# ME433_songwei.net
KiCad netlist of a schematic drawn in EAGLE
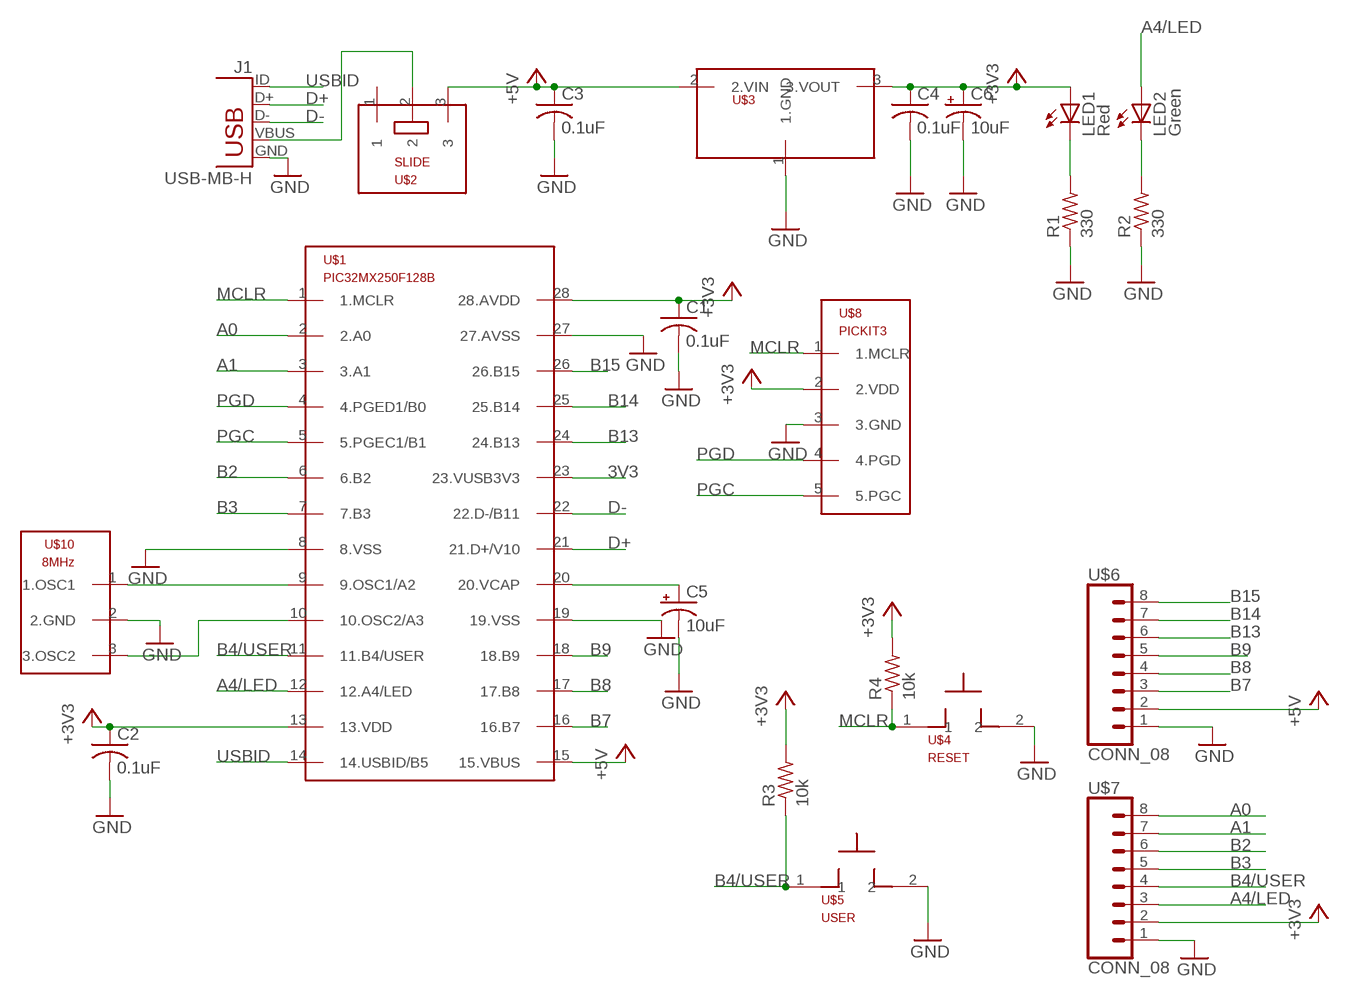
[diagram p0: schematic, sheet 1]

(export (version "E")
  (design (tool "Eeschema 10.0.6"))
  (components
    (comp (ref "C1")
      (value "0.1uF")
      (footprint "eagle-import:C025-025X050")
      (libsource (lib "eagle-import") (part "C-US025-025X050"))
    )
    (comp (ref "C2")
      (value "0.1uF")
      (footprint "eagle-import:C025-025X050")
      (libsource (lib "eagle-import") (part "C-US025-025X050"))
    )
    (comp (ref "C3")
      (value "0.1uF")
      (footprint "eagle-import:C025-025X050")
      (libsource (lib "eagle-import") (part "C-US025-025X050"))
    )
    (comp (ref "C4")
      (value "0.1uF")
      (footprint "eagle-import:C025-025X050")
      (libsource (lib "eagle-import") (part "C-US025-025X050"))
    )
    (comp (ref "C5")
      (value "10uF")
      (footprint "eagle-import:B45181B")
      (libsource (lib "eagle-import") (part "CPOL-USB45181B"))
    )
    (comp (ref "C6")
      (value "10uF")
      (footprint "eagle-import:B45181B")
      (libsource (lib "eagle-import") (part "CPOL-USB45181B"))
    )
    (comp (ref "J1")
      (value "USB-MB-H")
      (footprint "eagle-import:USB-MB-H")
      (libsource (lib "eagle-import") (part "USB-MB-H"))
    )
    (comp (ref "LED1")
      (value "Red")
      (footprint "eagle-import:LED3MM")
      (libsource (lib "eagle-import") (part "LED3MM"))
    )
    (comp (ref "LED2")
      (value "Green")
      (footprint "eagle-import:LED3MM")
      (libsource (lib "eagle-import") (part "LED3MM"))
    )
    (comp (ref "R1")
      (value "330")
      (footprint "eagle-import:0207_10")
      (libsource (lib "eagle-import") (part "R-US_0207/10"))
    )
    (comp (ref "R2")
      (value "330")
      (footprint "eagle-import:0207_10")
      (libsource (lib "eagle-import") (part "R-US_0207/10"))
    )
    (comp (ref "R3")
      (value "10k")
      (footprint "eagle-import:0207_10")
      (libsource (lib "eagle-import") (part "R-US_0207/10"))
    )
    (comp (ref "R4")
      (value "10k")
      (footprint "eagle-import:0207_10")
      (libsource (lib "eagle-import") (part "R-US_0207/10"))
    )
    (comp (ref "U$1")
      (value "PIC32MX250F128B")
      (footprint "eagle-import:DIL28-3")
      (libsource (lib "eagle-import") (part "PIC32MX250F128B"))
    )
    (comp (ref "U$2")
      (value "SLIDE")
      (footprint "eagle-import:SLIDE")
      (libsource (lib "eagle-import") (part "SLIDE"))
    )
    (comp (ref "U$3")
      (value "MCP1702")
      (footprint "eagle-import:TO92")
      (libsource (lib "eagle-import") (part "MCP1702"))
    )
    (comp (ref "U$4")
      (value "RESET")
      (footprint "eagle-import:PB")
      (libsource (lib "eagle-import") (part "PB"))
    )
    (comp (ref "U$5")
      (value "USER")
      (footprint "eagle-import:PB")
      (libsource (lib "eagle-import") (part "PB"))
    )
    (comp (ref "U$6")
      (value "CONN_08")
      (footprint "eagle-import:1X08")
      (libsource (lib "eagle-import") (part "CONN_08"))
    )
    (comp (ref "U$7")
      (value "CONN_08")
      (footprint "eagle-import:1X08")
      (libsource (lib "eagle-import") (part "CONN_08"))
    )
    (comp (ref "U$8")
      (value "PICKIT3")
      (footprint "eagle-import:1X05")
      (libsource (lib "eagle-import") (part "PICKIT3"))
    )
    (comp (ref "U$10")
      (value "8MHz")
      (footprint "eagle-import:OSC")
      (libsource (lib "eagle-import") (part "OSC"))
    )
  )
  (nets
    (net (code "1") (name "+3V3") (class "Default")
      (node (ref "C1") (pin "1") (pinfunction "1_1") (pintype "passive"))
      (node (ref "C2") (pin "1") (pinfunction "1_1") (pintype "passive"))
      (node (ref "C4") (pin "1") (pinfunction "1_1") (pintype "passive"))
      (node (ref "C6") (pin "+") (pinfunction "+_+") (pintype "passive"))
      (node (ref "LED1") (pin "A") (pinfunction "A_A") (pintype "passive"))
      (node (ref "R3") (pin "2") (pinfunction "2_2") (pintype "passive"))
      (node (ref "R4") (pin "2") (pinfunction "2_2") (pintype "passive"))
      (node (ref "U$1") (pin "13") (pinfunction "13.VDD_13") (pintype "bidirectional"))
      (node (ref "U$1") (pin "28") (pinfunction "28.AVDD_28") (pintype "bidirectional"))
      (node (ref "U$3") (pin "3") (pinfunction "3.VOUT_3") (pintype "bidirectional"))
      (node (ref "U$7") (pin "2") (pinfunction "2_2") (pintype "passive"))
      (node (ref "U$8") (pin "2") (pinfunction "2.VDD_2") (pintype "bidirectional"))
    )
    (net (code "2") (name "+5V") (class "Default")
      (node (ref "C3") (pin "1") (pinfunction "1_1") (pintype "passive"))
      (node (ref "U$1") (pin "15") (pinfunction "15.VBUS_15") (pintype "bidirectional"))
      (node (ref "U$2") (pin "3") (pinfunction "3_3") (pintype "bidirectional"))
      (node (ref "U$3") (pin "2") (pinfunction "2.VIN_2") (pintype "bidirectional"))
      (node (ref "U$6") (pin "2") (pinfunction "2_2") (pintype "passive"))
    )
    (net (code "3") (name "/3V3") (class "Default")
      (node (ref "U$1") (pin "23") (pinfunction "23.VUSB3V3_23") (pintype "bidirectional"))
    )
    (net (code "4") (name "/A0") (class "Default")
      (node (ref "U$1") (pin "2") (pinfunction "2.A0_2") (pintype "bidirectional"))
      (node (ref "U$7") (pin "8") (pinfunction "8_8") (pintype "passive"))
    )
    (net (code "5") (name "/A1") (class "Default")
      (node (ref "U$1") (pin "3") (pinfunction "3.A1_3") (pintype "bidirectional"))
      (node (ref "U$7") (pin "7") (pinfunction "7_7") (pintype "passive"))
    )
    (net (code "6") (name "/A4{slash}LED") (class "Default")
      (node (ref "LED2") (pin "A") (pinfunction "A_A") (pintype "passive"))
      (node (ref "U$1") (pin "12") (pinfunction "12.A4/LED_12") (pintype "bidirectional"))
      (node (ref "U$7") (pin "3") (pinfunction "3_3") (pintype "passive"))
    )
    (net (code "7") (name "/B2") (class "Default")
      (node (ref "U$1") (pin "6") (pinfunction "6.B2_6") (pintype "bidirectional"))
      (node (ref "U$7") (pin "6") (pinfunction "6_6") (pintype "passive"))
    )
    (net (code "8") (name "/B3") (class "Default")
      (node (ref "U$1") (pin "7") (pinfunction "7.B3_7") (pintype "bidirectional"))
      (node (ref "U$7") (pin "5") (pinfunction "5_5") (pintype "passive"))
    )
    (net (code "9") (name "/B4{slash}USER") (class "Default")
      (node (ref "R3") (pin "1") (pinfunction "1_1") (pintype "passive"))
      (node (ref "U$1") (pin "11") (pinfunction "11.B4/USER_11") (pintype "bidirectional"))
      (node (ref "U$5") (pin "1") (pinfunction "1_1") (pintype "bidirectional"))
      (node (ref "U$7") (pin "4") (pinfunction "4_4") (pintype "passive"))
    )
    (net (code "10") (name "/B7") (class "Default")
      (node (ref "U$1") (pin "16") (pinfunction "16.B7_16") (pintype "bidirectional"))
      (node (ref "U$6") (pin "3") (pinfunction "3_3") (pintype "passive"))
    )
    (net (code "11") (name "/B8") (class "Default")
      (node (ref "U$1") (pin "17") (pinfunction "17.B8_17") (pintype "bidirectional"))
      (node (ref "U$6") (pin "4") (pinfunction "4_4") (pintype "passive"))
    )
    (net (code "12") (name "/B9") (class "Default")
      (node (ref "U$1") (pin "18") (pinfunction "18.B9_18") (pintype "bidirectional"))
      (node (ref "U$6") (pin "5") (pinfunction "5_5") (pintype "passive"))
    )
    (net (code "13") (name "/B13") (class "Default")
      (node (ref "U$1") (pin "24") (pinfunction "24.B13_24") (pintype "bidirectional"))
      (node (ref "U$6") (pin "6") (pinfunction "6_6") (pintype "passive"))
    )
    (net (code "14") (name "/B14") (class "Default")
      (node (ref "U$1") (pin "25") (pinfunction "25.B14_25") (pintype "bidirectional"))
      (node (ref "U$6") (pin "7") (pinfunction "7_7") (pintype "passive"))
    )
    (net (code "15") (name "/B15") (class "Default")
      (node (ref "U$1") (pin "26") (pinfunction "26.B15_26") (pintype "bidirectional"))
      (node (ref "U$6") (pin "8") (pinfunction "8_8") (pintype "passive"))
    )
    (net (code "16") (name "/D+") (class "Default")
      (node (ref "J1") (pin "D+") (pinfunction "D+_D+") (pintype "bidirectional"))
      (node (ref "U$1") (pin "21") (pinfunction "21.D+/V10_21") (pintype "bidirectional"))
    )
    (net (code "17") (name "/D-") (class "Default")
      (node (ref "J1") (pin "D-") (pinfunction "D-_D-") (pintype "bidirectional"))
      (node (ref "U$1") (pin "22") (pinfunction "22.D-/B11_22") (pintype "bidirectional"))
    )
    (net (code "18") (name "/MCLR") (class "Default")
      (node (ref "R4") (pin "1") (pinfunction "1_1") (pintype "passive"))
      (node (ref "U$1") (pin "1") (pinfunction "1.MCLR_1") (pintype "bidirectional"))
      (node (ref "U$4") (pin "1") (pinfunction "1_1") (pintype "bidirectional"))
      (node (ref "U$8") (pin "1") (pinfunction "1.MCLR_1") (pintype "bidirectional"))
    )
    (net (code "19") (name "/PGC") (class "Default")
      (node (ref "U$1") (pin "5") (pinfunction "5.PGEC1/B1_5") (pintype "bidirectional"))
      (node (ref "U$8") (pin "5") (pinfunction "5.PGC_5") (pintype "bidirectional"))
    )
    (net (code "20") (name "/PGD") (class "Default")
      (node (ref "U$1") (pin "4") (pinfunction "4.PGED1/B0_4") (pintype "bidirectional"))
      (node (ref "U$8") (pin "4") (pinfunction "4.PGD_4") (pintype "bidirectional"))
    )
    (net (code "21") (name "/USBID") (class "Default")
      (node (ref "J1") (pin "ID") (pinfunction "ID_ID") (pintype "bidirectional"))
      (node (ref "U$1") (pin "14") (pinfunction "14.USBID/B5_14") (pintype "bidirectional"))
    )
    (net (code "22") (name "GND") (class "Default")
      (node (ref "C1") (pin "2") (pinfunction "2_2") (pintype "passive"))
      (node (ref "C2") (pin "2") (pinfunction "2_2") (pintype "passive"))
      (node (ref "C3") (pin "2") (pinfunction "2_2") (pintype "passive"))
      (node (ref "C4") (pin "2") (pinfunction "2_2") (pintype "passive"))
      (node (ref "C5") (pin "-") (pinfunction "-_-") (pintype "passive"))
      (node (ref "C6") (pin "-") (pinfunction "-_-") (pintype "passive"))
      (node (ref "J1") (pin "GND") (pinfunction "GND_GND") (pintype "bidirectional"))
      (node (ref "R1") (pin "1") (pinfunction "1_1") (pintype "passive"))
      (node (ref "R2") (pin "1") (pinfunction "1_1") (pintype "passive"))
      (node (ref "U$1") (pin "19") (pinfunction "19.VSS_19") (pintype "bidirectional"))
      (node (ref "U$1") (pin "27") (pinfunction "27.AVSS_27") (pintype "bidirectional"))
      (node (ref "U$1") (pin "8") (pinfunction "8.VSS_8") (pintype "bidirectional"))
      (node (ref "U$10") (pin "2") (pinfunction "2.GND_2") (pintype "bidirectional"))
      (node (ref "U$3") (pin "1") (pinfunction "1.GND_1") (pintype "bidirectional"))
      (node (ref "U$4") (pin "2") (pinfunction "2_2") (pintype "bidirectional"))
      (node (ref "U$5") (pin "2") (pinfunction "2_2") (pintype "bidirectional"))
      (node (ref "U$6") (pin "1") (pinfunction "1_1") (pintype "passive"))
      (node (ref "U$7") (pin "1") (pinfunction "1_1") (pintype "passive"))
      (node (ref "U$8") (pin "3") (pinfunction "3.GND_3") (pintype "bidirectional"))
    )
    (net (code "23") (name "Net-(J1-PadVBUS)") (class "Default")
      (node (ref "J1") (pin "VBUS") (pinfunction "VBUS_VBUS") (pintype "bidirectional"))
      (node (ref "U$2") (pin "2") (pinfunction "2_2") (pintype "bidirectional"))
    )
    (net (code "24") (name "Net-(LED1-C)") (class "Default")
      (node (ref "LED1") (pin "K") (pinfunction "C_K") (pintype "passive"))
      (node (ref "R1") (pin "2") (pinfunction "2_2") (pintype "passive"))
    )
    (net (code "25") (name "Net-(LED2-C)") (class "Default")
      (node (ref "LED2") (pin "K") (pinfunction "C_K") (pintype "passive"))
      (node (ref "R2") (pin "2") (pinfunction "2_2") (pintype "passive"))
    )
    (net (code "26") (name "Net-(U$1-9.OSC1{slash}A2)") (class "Default")
      (node (ref "U$1") (pin "9") (pinfunction "9.OSC1/A2_9") (pintype "bidirectional"))
      (node (ref "U$10") (pin "1") (pinfunction "1.OSC1_1") (pintype "bidirectional"))
    )
    (net (code "27") (name "Net-(U$1-10.OSC2{slash}A3)") (class "Default")
      (node (ref "U$1") (pin "10") (pinfunction "10.OSC2/A3_10") (pintype "bidirectional"))
      (node (ref "U$10") (pin "3") (pinfunction "3.OSC2_3") (pintype "bidirectional"))
    )
    (net (code "28") (name "Net-(U$1-20.VCAP)") (class "Default")
      (node (ref "C5") (pin "+") (pinfunction "+_+") (pintype "passive"))
      (node (ref "U$1") (pin "20") (pinfunction "20.VCAP_20") (pintype "bidirectional"))
    )
    (net (code "29") (name "unconnected-(U$2-Pad1)") (class "Default")
      (node (ref "U$2") (pin "1") (pinfunction "1_1") (pintype "bidirectional"))
    )
  )
)
